# Rotator.net
KiCad netlist of a schematic drawn in EAGLE
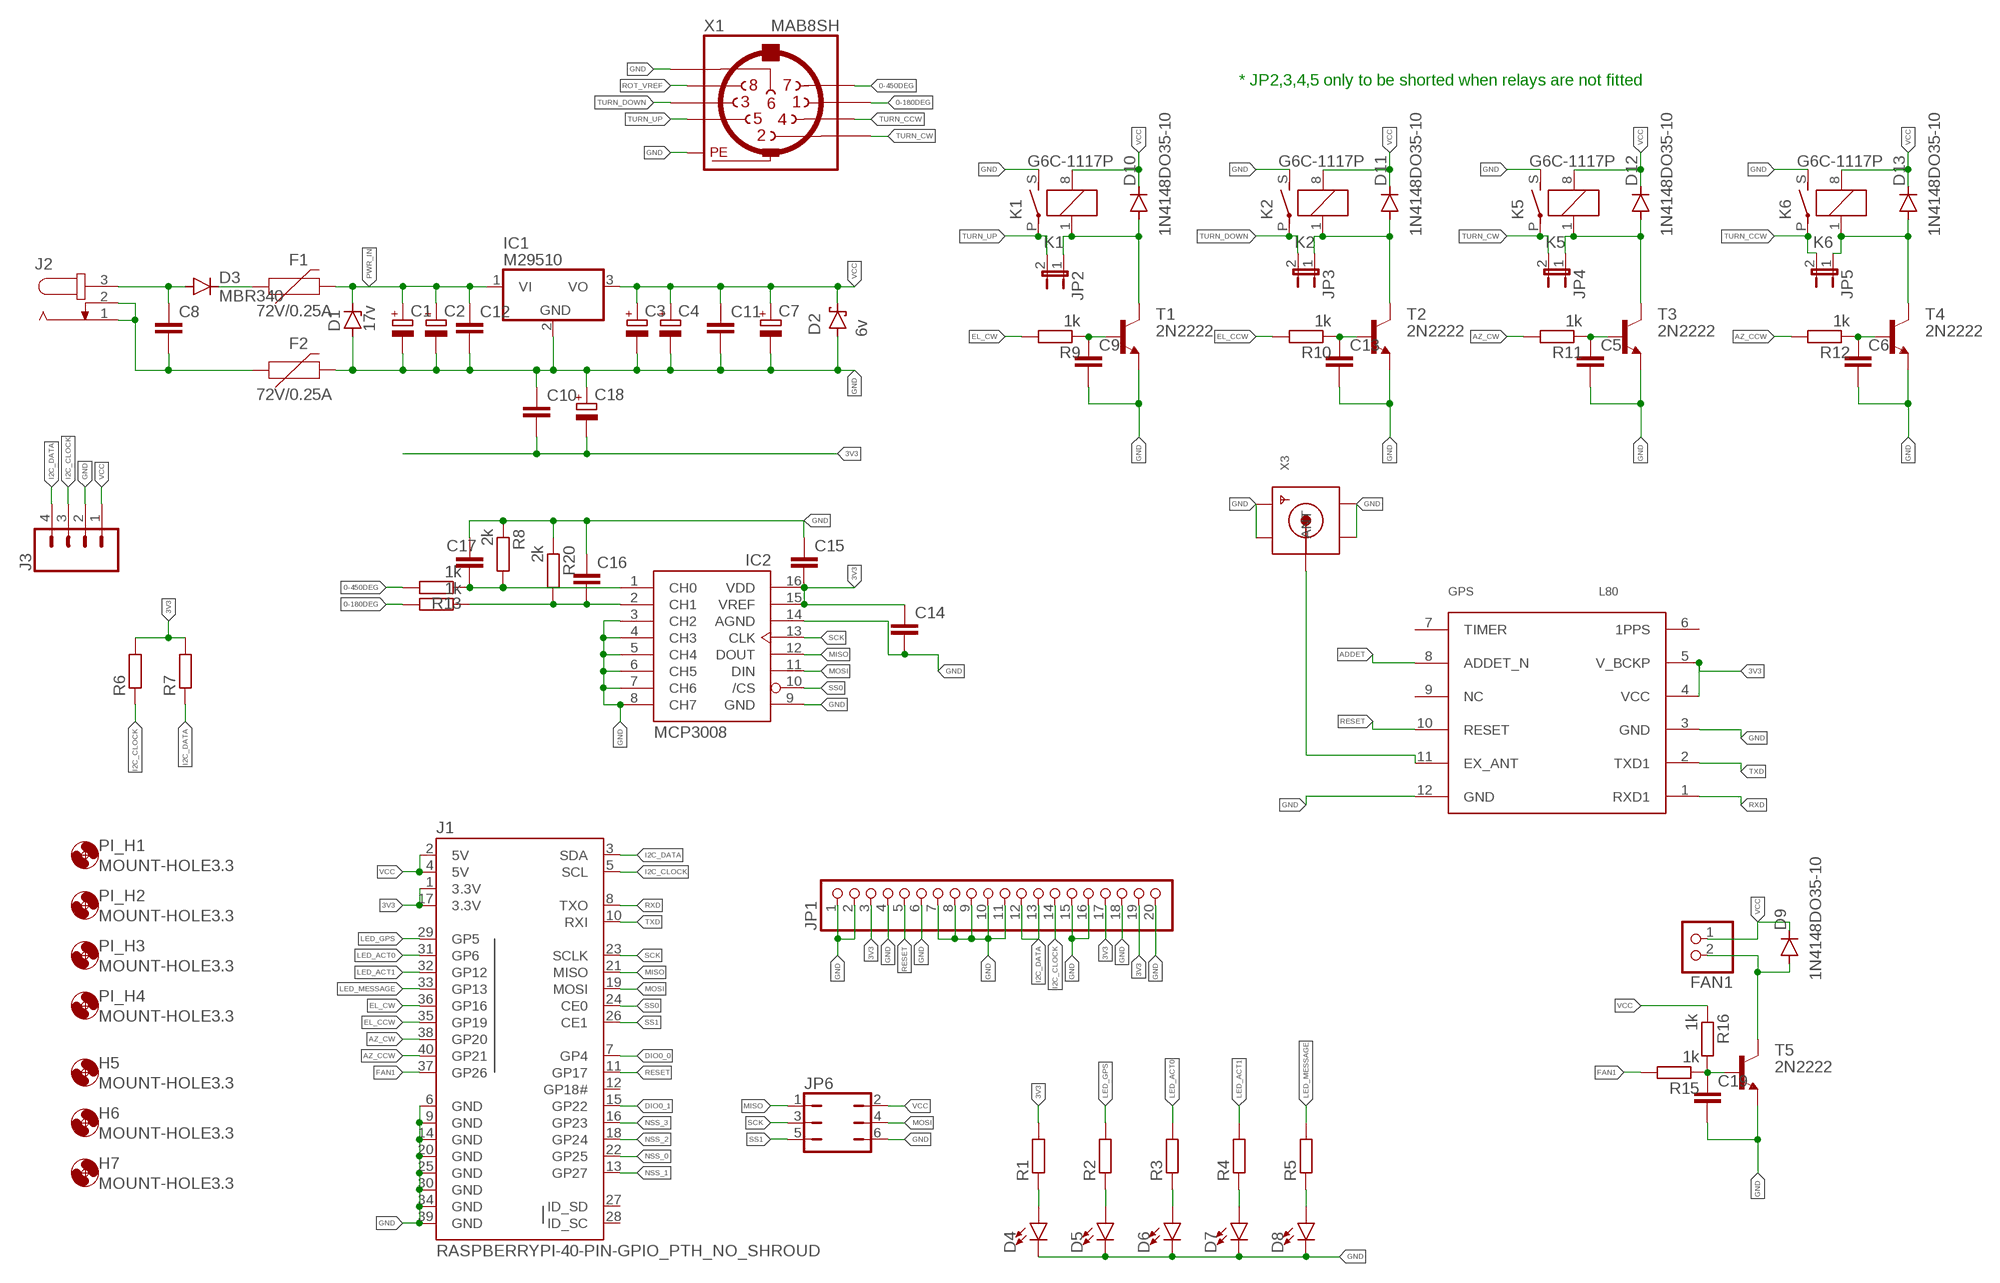
[diagram p0: schematic, sheet 1]

(export (version "E")
  (design (tool "Eeschema 10.0.6"))
  (components
    (comp (ref "C1")
      (value "CPOL-EUE5-8.5")
      (footprint "eagle-import:E5-8,5")
      (libsource (lib "eagle-import") (part "CPOL-EUE5-8.5"))
    )
    (comp (ref "C2")
      (value "CPOL-EUE5-8.5")
      (footprint "eagle-import:E5-8,5")
      (libsource (lib "eagle-import") (part "CPOL-EUE5-8.5"))
    )
    (comp (ref "C3")
      (value "CPOL-EUE2.5-7")
      (footprint "eagle-import:E2,5-7")
      (libsource (lib "eagle-import") (part "CPOL-EUE2.5-7"))
    )
    (comp (ref "C4")
      (value "CPOL-EUE2.5-7")
      (footprint "eagle-import:E2,5-7")
      (libsource (lib "eagle-import") (part "CPOL-EUE2.5-7"))
    )
    (comp (ref "C5")
      (value "C-EU050-025X075")
      (footprint "eagle-import:C050-025X075")
      (libsource (lib "eagle-import") (part "C-EU050-025X075"))
    )
    (comp (ref "C6")
      (value "C-EU050-025X075")
      (footprint "eagle-import:C050-025X075")
      (libsource (lib "eagle-import") (part "C-EU050-025X075"))
    )
    (comp (ref "C7")
      (value "CPOL-EUE2.5-7")
      (footprint "eagle-import:E2,5-7")
      (libsource (lib "eagle-import") (part "CPOL-EUE2.5-7"))
    )
    (comp (ref "C8")
      (value "C-EU050-025X075")
      (footprint "eagle-import:C050-025X075")
      (libsource (lib "eagle-import") (part "C-EU050-025X075"))
    )
    (comp (ref "C9")
      (value "C-EU050-025X075")
      (footprint "eagle-import:C050-025X075")
      (libsource (lib "eagle-import") (part "C-EU050-025X075"))
    )
    (comp (ref "C10")
      (value "C-EU050-025X075")
      (footprint "eagle-import:C050-025X075")
      (libsource (lib "eagle-import") (part "C-EU050-025X075"))
    )
    (comp (ref "C11")
      (value "C-EU050-025X075")
      (footprint "eagle-import:C050-025X075")
      (libsource (lib "eagle-import") (part "C-EU050-025X075"))
    )
    (comp (ref "C12")
      (value "C-EU050-025X075")
      (footprint "eagle-import:C050-025X075")
      (libsource (lib "eagle-import") (part "C-EU050-025X075"))
    )
    (comp (ref "C13")
      (value "C-EU050-025X075")
      (footprint "eagle-import:C050-025X075")
      (libsource (lib "eagle-import") (part "C-EU050-025X075"))
    )
    (comp (ref "C14")
      (value "C-EU050-025X075")
      (footprint "eagle-import:C050-025X075")
      (libsource (lib "eagle-import") (part "C-EU050-025X075"))
    )
    (comp (ref "C15")
      (value "C-EU050-025X075")
      (footprint "eagle-import:C050-025X075")
      (libsource (lib "eagle-import") (part "C-EU050-025X075"))
    )
    (comp (ref "C16")
      (value "C-EU050-025X075")
      (footprint "eagle-import:C050-025X075")
      (libsource (lib "eagle-import") (part "C-EU050-025X075"))
    )
    (comp (ref "C17")
      (value "C-EU050-025X075")
      (footprint "eagle-import:C050-025X075")
      (libsource (lib "eagle-import") (part "C-EU050-025X075"))
    )
    (comp (ref "C18")
      (value "CPOL-EUE2.5-7")
      (footprint "eagle-import:E2,5-7")
      (libsource (lib "eagle-import") (part "CPOL-EUE2.5-7"))
    )
    (comp (ref "C19")
      (value "C-EU050-025X075")
      (footprint "eagle-import:C050-025X075")
      (libsource (lib "eagle-import") (part "C-EU050-025X075"))
    )
    (comp (ref "D1")
      (value "17v")
      (footprint "eagle-import:F126Z12")
      (libsource (lib "eagle-import") (part "ZENER-DIODEF126-12"))
    )
    (comp (ref "D2")
      (value "6v")
      (footprint "eagle-import:F126Z12")
      (libsource (lib "eagle-import") (part "SCHOTTKY-DIODEF126Z12"))
    )
    (comp (ref "D3")
      (value "MBR340")
      (footprint "eagle-import:DO201-15")
      (libsource (lib "eagle-import") (part "1N5400"))
    )
    (comp (ref "D4")
      (value "LED3MM")
      (footprint "eagle-import:LED_3MM")
      (libsource (lib "eagle-import") (part "LED3MM"))
    )
    (comp (ref "D5")
      (value "LED3MM")
      (footprint "eagle-import:LED_3MM")
      (libsource (lib "eagle-import") (part "LED3MM"))
    )
    (comp (ref "D6")
      (value "LED3MM")
      (footprint "eagle-import:LED_3MM")
      (libsource (lib "eagle-import") (part "LED3MM"))
    )
    (comp (ref "D7")
      (value "LED3MM")
      (footprint "eagle-import:LED_3MM")
      (libsource (lib "eagle-import") (part "LED3MM"))
    )
    (comp (ref "D8")
      (value "LED3MM")
      (footprint "eagle-import:LED_3MM")
      (libsource (lib "eagle-import") (part "LED3MM"))
    )
    (comp (ref "D9")
      (value "1N4148DO35-10")
      (footprint "eagle-import:DO35-10")
      (libsource (lib "eagle-import") (part "1N4148DO35-10"))
    )
    (comp (ref "D10")
      (value "1N4148DO35-10")
      (footprint "eagle-import:DO35-10")
      (libsource (lib "eagle-import") (part "1N4148DO35-10"))
    )
    (comp (ref "D11")
      (value "1N4148DO35-10")
      (footprint "eagle-import:DO35-10")
      (libsource (lib "eagle-import") (part "1N4148DO35-10"))
    )
    (comp (ref "D12")
      (value "1N4148DO35-10")
      (footprint "eagle-import:DO35-10")
      (libsource (lib "eagle-import") (part "1N4148DO35-10"))
    )
    (comp (ref "D13")
      (value "1N4148DO35-10")
      (footprint "eagle-import:DO35-10")
      (libsource (lib "eagle-import") (part "1N4148DO35-10"))
    )
    (comp (ref "F1")
      (value "72V/0.25A")
      (footprint "eagle-import:PTH")
      (libsource (lib "eagle-import") (part "PPTC_PTH"))
    )
    (comp (ref "F2")
      (value "72V/0.25A")
      (footprint "eagle-import:PTH")
      (libsource (lib "eagle-import") (part "PPTC_PTH"))
    )
    (comp (ref "FAN1")
      (value "JST_2PIN-THM")
      (footprint "eagle-import:JST-PH-2-THM")
      (libsource (lib "eagle-import") (part "JST_2PIN-THM"))
    )
    (comp (ref "GPS")
      (value "L80")
      (footprint "eagle-import:L80")
      (libsource (lib "eagle-import") (part "L80"))
    )
    (comp (ref "H5")
      (value "MOUNT-HOLE3.3")
      (footprint "eagle-import:3,3")
      (libsource (lib "eagle-import") (part "MOUNT-HOLE3.3"))
    )
    (comp (ref "H6")
      (value "MOUNT-HOLE3.3")
      (footprint "eagle-import:3,3")
      (libsource (lib "eagle-import") (part "MOUNT-HOLE3.3"))
    )
    (comp (ref "H7")
      (value "MOUNT-HOLE3.3")
      (footprint "eagle-import:3,3")
      (libsource (lib "eagle-import") (part "MOUNT-HOLE3.3"))
    )
    (comp (ref "IC1")
      (value "M29510")
      (footprint "eagle-import:TO220H")
      (libsource (lib "eagle-import") (part "78T05"))
    )
    (comp (ref "IC2")
      (value "MCP3008")
      (footprint "eagle-import:DIL16")
      (libsource (lib "eagle-import") (part "MCP3008"))
    )
    (comp (ref "J1")
      (value "RASPBERRYPI-40-PIN-GPIO_PTH_NO_SHROUD")
      (footprint "eagle-import:2X20")
      (libsource (lib "eagle-import") (part "RASPBERRYPI-40-PIN-GPIO_PTH_NO_SHROUD"))
    )
    (comp (ref "J2")
      (value "JACK-PLUG0")
      (footprint "eagle-import:SPC4077")
      (libsource (lib "eagle-import") (part "JACK-PLUG0"))
    )
    (comp (ref "J3")
      (value "CONN_04")
      (footprint "eagle-import:1X04")
      (libsource (lib "eagle-import") (part "CONN_04"))
    )
    (comp (ref "JP1")
      (value "PINHD-1X20")
      (footprint "eagle-import:1X20")
      (libsource (lib "eagle-import") (part "PINHD-1X20"))
    )
    (comp (ref "JP2")
      (value "JP1E")
      (footprint "eagle-import:JP1")
      (libsource (lib "eagle-import") (part "JP1E"))
    )
    (comp (ref "JP3")
      (value "JP1E")
      (footprint "eagle-import:JP1")
      (libsource (lib "eagle-import") (part "JP1E"))
    )
    (comp (ref "JP4")
      (value "JP1E")
      (footprint "eagle-import:JP1")
      (libsource (lib "eagle-import") (part "JP1E"))
    )
    (comp (ref "JP5")
      (value "JP1E")
      (footprint "eagle-import:JP1")
      (libsource (lib "eagle-import") (part "JP1E"))
    )
    (comp (ref "JP6")
      (value "JP3Q")
      (footprint "eagle-import:JP3Q")
      (libsource (lib "eagle-import") (part "JP3Q"))
    )
    (comp (ref "K1")
      (value "G6C-1117P")
      (footprint "eagle-import:G6C-1117P")
      (libsource (lib "eagle-import") (part "G6C-1117P"))
    )
    (comp (ref "K2")
      (value "G6C-1117P")
      (footprint "eagle-import:G6C-1117P")
      (libsource (lib "eagle-import") (part "G6C-1117P"))
    )
    (comp (ref "K5")
      (value "G6C-1117P")
      (footprint "eagle-import:G6C-1117P")
      (libsource (lib "eagle-import") (part "G6C-1117P"))
    )
    (comp (ref "K6")
      (value "G6C-1117P")
      (footprint "eagle-import:G6C-1117P")
      (libsource (lib "eagle-import") (part "G6C-1117P"))
    )
    (comp (ref "PI_H1")
      (value "MOUNT-HOLE3.3")
      (footprint "eagle-import:3,3")
      (libsource (lib "eagle-import") (part "MOUNT-HOLE3.3"))
    )
    (comp (ref "PI_H2")
      (value "MOUNT-HOLE3.3")
      (footprint "eagle-import:3,3")
      (libsource (lib "eagle-import") (part "MOUNT-HOLE3.3"))
    )
    (comp (ref "PI_H3")
      (value "MOUNT-HOLE3.3")
      (footprint "eagle-import:3,3")
      (libsource (lib "eagle-import") (part "MOUNT-HOLE3.3"))
    )
    (comp (ref "PI_H4")
      (value "MOUNT-HOLE3.3")
      (footprint "eagle-import:3,3")
      (libsource (lib "eagle-import") (part "MOUNT-HOLE3.3"))
    )
    (comp (ref "R1")
      (value "R-EU_0207/10")
      (footprint "eagle-import:0207_10")
      (libsource (lib "eagle-import") (part "R-EU_0207/10"))
    )
    (comp (ref "R2")
      (value "R-EU_0207/10")
      (footprint "eagle-import:0207_10")
      (libsource (lib "eagle-import") (part "R-EU_0207/10"))
    )
    (comp (ref "R3")
      (value "R-EU_0207/10")
      (footprint "eagle-import:0207_10")
      (libsource (lib "eagle-import") (part "R-EU_0207/10"))
    )
    (comp (ref "R4")
      (value "R-EU_0207/10")
      (footprint "eagle-import:0207_10")
      (libsource (lib "eagle-import") (part "R-EU_0207/10"))
    )
    (comp (ref "R5")
      (value "R-EU_0207/10")
      (footprint "eagle-import:0207_10")
      (libsource (lib "eagle-import") (part "R-EU_0207/10"))
    )
    (comp (ref "R6")
      (value "R-EU_0207/10")
      (footprint "eagle-import:0207_10")
      (libsource (lib "eagle-import") (part "R-EU_0207/10"))
    )
    (comp (ref "R7")
      (value "R-EU_0207/10")
      (footprint "eagle-import:0207_10")
      (libsource (lib "eagle-import") (part "R-EU_0207/10"))
    )
    (comp (ref "R8")
      (value "2k")
      (footprint "eagle-import:0207_10")
      (libsource (lib "eagle-import") (part "R-EU_0207/10"))
    )
    (comp (ref "R9")
      (value "1k")
      (footprint "eagle-import:0207_10")
      (libsource (lib "eagle-import") (part "R-EU_0207/10"))
    )
    (comp (ref "R10")
      (value "1k")
      (footprint "eagle-import:0207_10")
      (libsource (lib "eagle-import") (part "R-EU_0207/10"))
    )
    (comp (ref "R11")
      (value "1k")
      (footprint "eagle-import:0207_10")
      (libsource (lib "eagle-import") (part "R-EU_0207/10"))
    )
    (comp (ref "R12")
      (value "1k")
      (footprint "eagle-import:0207_10")
      (libsource (lib "eagle-import") (part "R-EU_0207/10"))
    )
    (comp (ref "R13")
      (value "1k")
      (footprint "eagle-import:0207_10")
      (libsource (lib "eagle-import") (part "R-EU_0207/10"))
    )
    (comp (ref "R14")
      (value "1k")
      (footprint "eagle-import:0207_10")
      (libsource (lib "eagle-import") (part "R-EU_0207/10"))
    )
    (comp (ref "R15")
      (value "1k")
      (footprint "eagle-import:0207_10")
      (libsource (lib "eagle-import") (part "R-EU_0207/10"))
    )
    (comp (ref "R16")
      (value "1k")
      (footprint "eagle-import:0207_10")
      (libsource (lib "eagle-import") (part "R-EU_0207/10"))
    )
    (comp (ref "R20")
      (value "2k")
      (footprint "eagle-import:0207_10")
      (libsource (lib "eagle-import") (part "R-EU_0207/10"))
    )
    (comp (ref "T1")
      (value "2N2222")
      (footprint "eagle-import:TO92-EBC-OVAL")
      (libsource (lib "eagle-import") (part "2N2222"))
    )
    (comp (ref "T2")
      (value "2N2222")
      (footprint "eagle-import:TO92-EBC-OVAL")
      (libsource (lib "eagle-import") (part "2N2222"))
    )
    (comp (ref "T3")
      (value "2N2222")
      (footprint "eagle-import:TO92-EBC-OVAL")
      (libsource (lib "eagle-import") (part "2N2222"))
    )
    (comp (ref "T4")
      (value "2N2222")
      (footprint "eagle-import:TO92-EBC-OVAL")
      (libsource (lib "eagle-import") (part "2N2222"))
    )
    (comp (ref "T5")
      (value "2N2222")
      (footprint "eagle-import:TO92-EBC-OVAL")
      (libsource (lib "eagle-import") (part "2N2222"))
    )
    (comp (ref "X1")
      (value "MAB8SH")
      (footprint "eagle-import:MAB8SH")
      (fields (field (name "MF") "FARNELL") (field (name "MPN") "MAB 8 SH"))
      (libsource (lib "eagle-import") (part "MAB8SH"))
    )
    (comp (ref "X3")
      (value "SMACONNECTOR_EDGE")
      (footprint "eagle-import:SMA_EDGELAUNCH")
      (libsource (lib "eagle-import") (part "SMACONNECTOR_EDGE"))
    )
  )
  (nets
    (net (code "1") (name "0-180DEG") (class "Default")
      (node (ref "R14") (pin "2") (pinfunction "2_2") (pintype "passive"))
      (node (ref "X1") (pin "1") (pinfunction "1_1") (pintype "passive"))
    )
    (net (code "2") (name "0-450DEG") (class "Default")
      (node (ref "R13") (pin "2") (pinfunction "2_2") (pintype "passive"))
      (node (ref "X1") (pin "7") (pinfunction "7_7") (pintype "passive"))
    )
    (net (code "3") (name "3V3") (class "Default")
      (node (ref "C10") (pin "2") (pinfunction "2_2") (pintype "passive"))
      (node (ref "C14") (pin "1") (pinfunction "1_1") (pintype "passive"))
      (node (ref "C15") (pin "2") (pinfunction "2_2") (pintype "passive"))
      (node (ref "C18") (pin "-") (pinfunction "-_-") (pintype "passive"))
      (node (ref "GPS") (pin "4") (pinfunction "VCC_4") (pintype "bidirectional"))
      (node (ref "GPS") (pin "5") (pinfunction "V_BCKP_5") (pintype "bidirectional"))
      (node (ref "IC2") (pin "15") (pinfunction "VREF_15") (pintype "input"))
      (node (ref "IC2") (pin "16") (pinfunction "VDD_16") (pintype "power_in"))
      (node (ref "J1") (pin "1") (pinfunction "3.3V_1") (pintype "power_in"))
      (node (ref "J1") (pin "17") (pinfunction "3.3V_17") (pintype "power_in"))
      (node (ref "JP1") (pin "17") (pinfunction "17_17") (pintype "passive"))
      (node (ref "JP1") (pin "19") (pinfunction "19_19") (pintype "passive"))
      (node (ref "JP1") (pin "3") (pinfunction "3_3") (pintype "passive"))
      (node (ref "R1") (pin "2") (pinfunction "2_2") (pintype "passive"))
      (node (ref "R6") (pin "2") (pinfunction "2_2") (pintype "passive"))
      (node (ref "R7") (pin "2") (pinfunction "2_2") (pintype "passive"))
    )
    (net (code "4") (name "ADDET") (class "Default")
      (node (ref "GPS") (pin "8") (pinfunction "ADDET_N_8") (pintype "bidirectional"))
    )
    (net (code "5") (name "AZ_CCW") (class "Default")
      (node (ref "J1") (pin "40") (pinfunction "GP21_40") (pintype "bidirectional"))
      (node (ref "R12") (pin "2") (pinfunction "2_2") (pintype "passive"))
    )
    (net (code "6") (name "AZ_CW") (class "Default")
      (node (ref "J1") (pin "38") (pinfunction "GP20_38") (pintype "bidirectional"))
      (node (ref "R11") (pin "2") (pinfunction "2_2") (pintype "passive"))
    )
    (net (code "7") (name "DIO0_0") (class "Default")
      (node (ref "J1") (pin "7") (pinfunction "GP4_7") (pintype "bidirectional"))
    )
    (net (code "8") (name "DIO0_1") (class "Default")
      (node (ref "J1") (pin "15") (pinfunction "GP22_15") (pintype "bidirectional"))
    )
    (net (code "9") (name "EL_CCW") (class "Default")
      (node (ref "J1") (pin "35") (pinfunction "GP19_35") (pintype "bidirectional"))
      (node (ref "R10") (pin "2") (pinfunction "2_2") (pintype "passive"))
    )
    (net (code "10") (name "EL_CW") (class "Default")
      (node (ref "J1") (pin "36") (pinfunction "GP16_36") (pintype "bidirectional"))
      (node (ref "R9") (pin "2") (pinfunction "2_2") (pintype "passive"))
    )
    (net (code "11") (name "FAN1") (class "Default")
      (node (ref "J1") (pin "37") (pinfunction "GP26_37") (pintype "bidirectional"))
      (node (ref "R15") (pin "2") (pinfunction "2_2") (pintype "passive"))
    )
    (net (code "12") (name "GND") (class "Default")
      (node (ref "C1") (pin "-") (pinfunction "-_-") (pintype "passive"))
      (node (ref "C10") (pin "1") (pinfunction "1_1") (pintype "passive"))
      (node (ref "C11") (pin "2") (pinfunction "2_2") (pintype "passive"))
      (node (ref "C12") (pin "2") (pinfunction "2_2") (pintype "passive"))
      (node (ref "C13") (pin "2") (pinfunction "2_2") (pintype "passive"))
      (node (ref "C14") (pin "2") (pinfunction "2_2") (pintype "passive"))
      (node (ref "C15") (pin "1") (pinfunction "1_1") (pintype "passive"))
      (node (ref "C16") (pin "1") (pinfunction "1_1") (pintype "passive"))
      (node (ref "C17") (pin "1") (pinfunction "1_1") (pintype "passive"))
      (node (ref "C18") (pin "+") (pinfunction "+_+") (pintype "passive"))
      (node (ref "C19") (pin "2") (pinfunction "2_2") (pintype "passive"))
      (node (ref "C2") (pin "-") (pinfunction "-_-") (pintype "passive"))
      (node (ref "C3") (pin "-") (pinfunction "-_-") (pintype "passive"))
      (node (ref "C4") (pin "-") (pinfunction "-_-") (pintype "passive"))
      (node (ref "C5") (pin "2") (pinfunction "2_2") (pintype "passive"))
      (node (ref "C6") (pin "2") (pinfunction "2_2") (pintype "passive"))
      (node (ref "C7") (pin "-") (pinfunction "-_-") (pintype "passive"))
      (node (ref "C9") (pin "2") (pinfunction "2_2") (pintype "passive"))
      (node (ref "D1") (pin "A") (pinfunction "A_A") (pintype "passive"))
      (node (ref "D2") (pin "A") (pinfunction "A_A") (pintype "passive"))
      (node (ref "D4") (pin "K") (pinfunction "C_K") (pintype "passive"))
      (node (ref "D5") (pin "K") (pinfunction "C_K") (pintype "passive"))
      (node (ref "D6") (pin "K") (pinfunction "C_K") (pintype "passive"))
      (node (ref "D7") (pin "K") (pinfunction "C_K") (pintype "passive"))
      (node (ref "D8") (pin "K") (pinfunction "C_K") (pintype "passive"))
      (node (ref "F2") (pin "P$2") (pinfunction "2_P$2") (pintype "bidirectional"))
      (node (ref "GPS") (pin "12") (pinfunction "GND_12") (pintype "bidirectional"))
      (node (ref "GPS") (pin "3") (pinfunction "GND_3") (pintype "bidirectional"))
      (node (ref "IC1") (pin "2") (pinfunction "GND_2") (pintype "passive"))
      (node (ref "IC2") (pin "14") (pinfunction "AGND_14") (pintype "power_in"))
      (node (ref "IC2") (pin "3") (pinfunction "CH2_3") (pintype "input"))
      (node (ref "IC2") (pin "4") (pinfunction "CH3_4") (pintype "input"))
      (node (ref "IC2") (pin "5") (pinfunction "CH4_5") (pintype "input"))
      (node (ref "IC2") (pin "6") (pinfunction "CH5_6") (pintype "input"))
      (node (ref "IC2") (pin "7") (pinfunction "CH6_7") (pintype "input"))
      (node (ref "IC2") (pin "8") (pinfunction "CH7_8") (pintype "input"))
      (node (ref "IC2") (pin "9") (pinfunction "GND_9") (pintype "power_in"))
      (node (ref "J1") (pin "14") (pinfunction "GND_14") (pintype "power_in"))
      (node (ref "J1") (pin "20") (pinfunction "GND_20") (pintype "power_in"))
      (node (ref "J1") (pin "25") (pinfunction "GND_25") (pintype "power_in"))
      (node (ref "J1") (pin "30") (pinfunction "GND_30") (pintype "power_in"))
      (node (ref "J1") (pin "34") (pinfunction "GND_34") (pintype "power_in"))
      (node (ref "J1") (pin "39") (pinfunction "GND_39") (pintype "power_in"))
      (node (ref "J1") (pin "6") (pinfunction "GND_6") (pintype "power_in"))
      (node (ref "J1") (pin "9") (pinfunction "GND_9") (pintype "power_in"))
      (node (ref "J3") (pin "2") (pinfunction "2_2") (pintype "passive"))
      (node (ref "JP1") (pin "1") (pinfunction "1_1") (pintype "passive"))
      (node (ref "JP1") (pin "10") (pinfunction "10_10") (pintype "passive"))
      (node (ref "JP1") (pin "11") (pinfunction "11_11") (pintype "passive"))
      (node (ref "JP1") (pin "15") (pinfunction "15_15") (pintype "passive"))
      (node (ref "JP1") (pin "16") (pinfunction "16_16") (pintype "passive"))
      (node (ref "JP1") (pin "18") (pinfunction "18_18") (pintype "passive"))
      (node (ref "JP1") (pin "2") (pinfunction "2_2") (pintype "passive"))
      (node (ref "JP1") (pin "20") (pinfunction "20_20") (pintype "passive"))
      (node (ref "JP1") (pin "4") (pinfunction "4_4") (pintype "passive"))
      (node (ref "JP1") (pin "6") (pinfunction "6_6") (pintype "passive"))
      (node (ref "JP1") (pin "7") (pinfunction "7_7") (pintype "passive"))
      (node (ref "JP1") (pin "8") (pinfunction "8_8") (pintype "passive"))
      (node (ref "JP1") (pin "9") (pinfunction "9_9") (pintype "passive"))
      (node (ref "JP6") (pin "6") (pinfunction "6_6") (pintype "passive"))
      (node (ref "K1") (pin "S") (pinfunction "S_S") (pintype "passive"))
      (node (ref "K2") (pin "S") (pinfunction "S_S") (pintype "passive"))
      (node (ref "K5") (pin "S") (pinfunction "S_S") (pintype "passive"))
      (node (ref "K6") (pin "S") (pinfunction "S_S") (pintype "passive"))
      (node (ref "R20") (pin "1") (pinfunction "1_1") (pintype "passive"))
      (node (ref "R8") (pin "1") (pinfunction "1_1") (pintype "passive"))
      (node (ref "T1") (pin "E") (pinfunction "E_E") (pintype "passive"))
      (node (ref "T2") (pin "E") (pinfunction "E_E") (pintype "passive"))
      (node (ref "T3") (pin "E") (pinfunction "E_E") (pintype "passive"))
      (node (ref "T4") (pin "E") (pinfunction "E_E") (pintype "passive"))
      (node (ref "T5") (pin "E") (pinfunction "E_E") (pintype "passive"))
      (node (ref "X1") (pin "6") (pinfunction "6_6") (pintype "passive"))
      (node (ref "X1") (pin "PE") (pinfunction "PE_PE") (pintype "power_in"))
      (node (ref "X1") (pin "PE@") (pinfunction "PE_PE@") (pintype "power_in"))
      (node (ref "X3") (pin "GND@1") (pinfunction "GND4_GND@1") (pintype "power_in"))
      (node (ref "X3") (pin "GND@2") (pinfunction "GND3_GND@2") (pintype "power_in"))
      (node (ref "X3") (pin "GND@3") (pinfunction "GND2_GND@3") (pintype "power_in"))
      (node (ref "X3") (pin "GND@4") (pinfunction "GND1_GND@4") (pintype "power_in"))
    )
    (net (code "13") (name "I2C_CLOCK") (class "Default")
      (node (ref "J1") (pin "5") (pinfunction "SCL_5") (pintype "bidirectional"))
      (node (ref "J3") (pin "3") (pinfunction "3_3") (pintype "passive"))
      (node (ref "JP1") (pin "14") (pinfunction "14_14") (pintype "passive"))
      (node (ref "R6") (pin "1") (pinfunction "1_1") (pintype "passive"))
    )
    (net (code "14") (name "I2C_DATA") (class "Default")
      (node (ref "J1") (pin "3") (pinfunction "SDA_3") (pintype "bidirectional"))
      (node (ref "J3") (pin "4") (pinfunction "4_4") (pintype "passive"))
      (node (ref "JP1") (pin "12") (pinfunction "12_12") (pintype "passive"))
      (node (ref "JP1") (pin "13") (pinfunction "13_13") (pintype "passive"))
      (node (ref "R7") (pin "1") (pinfunction "1_1") (pintype "passive"))
    )
    (net (code "15") (name "LED_ACT0") (class "Default")
      (node (ref "J1") (pin "31") (pinfunction "GP6_31") (pintype "bidirectional"))
      (node (ref "R3") (pin "2") (pinfunction "2_2") (pintype "passive"))
    )
    (net (code "16") (name "LED_ACT1") (class "Default")
      (node (ref "J1") (pin "32") (pinfunction "GP12_32") (pintype "bidirectional"))
      (node (ref "R4") (pin "2") (pinfunction "2_2") (pintype "passive"))
    )
    (net (code "17") (name "LED_GPS") (class "Default")
      (node (ref "J1") (pin "29") (pinfunction "GP5_29") (pintype "bidirectional"))
      (node (ref "R2") (pin "2") (pinfunction "2_2") (pintype "passive"))
    )
    (net (code "18") (name "LED_MESSAGE") (class "Default")
      (node (ref "J1") (pin "33") (pinfunction "GP13_33") (pintype "bidirectional"))
      (node (ref "R5") (pin "2") (pinfunction "2_2") (pintype "passive"))
    )
    (net (code "19") (name "MISO") (class "Default")
      (node (ref "IC2") (pin "12") (pinfunction "DOUT_12") (pintype "output"))
      (node (ref "J1") (pin "21") (pinfunction "MISO_21") (pintype "input"))
      (node (ref "JP6") (pin "1") (pinfunction "1_1") (pintype "passive"))
    )
    (net (code "20") (name "MOSI") (class "Default")
      (node (ref "IC2") (pin "11") (pinfunction "DIN_11") (pintype "input"))
      (node (ref "J1") (pin "19") (pinfunction "MOSI_19") (pintype "output"))
      (node (ref "JP6") (pin "4") (pinfunction "4_4") (pintype "passive"))
    )
    (net (code "21") (name "NSS_0") (class "Default")
      (node (ref "J1") (pin "22") (pinfunction "GP25_22") (pintype "bidirectional"))
    )
    (net (code "22") (name "NSS_1") (class "Default")
      (node (ref "J1") (pin "13") (pinfunction "GP27_13") (pintype "bidirectional"))
    )
    (net (code "23") (name "NSS_2") (class "Default")
      (node (ref "J1") (pin "18") (pinfunction "GP24_18") (pintype "bidirectional"))
    )
    (net (code "24") (name "NSS_3") (class "Default")
      (node (ref "J1") (pin "16") (pinfunction "GP23_16") (pintype "bidirectional"))
    )
    (net (code "25") (name "Net-(C5-Pad1)") (class "Default")
      (node (ref "C5") (pin "1") (pinfunction "1_1") (pintype "passive"))
      (node (ref "R11") (pin "1") (pinfunction "1_1") (pintype "passive"))
      (node (ref "T3") (pin "B") (pinfunction "B_B") (pintype "passive"))
    )
    (net (code "26") (name "Net-(C6-Pad1)") (class "Default")
      (node (ref "C6") (pin "1") (pinfunction "1_1") (pintype "passive"))
      (node (ref "R12") (pin "1") (pinfunction "1_1") (pintype "passive"))
      (node (ref "T4") (pin "B") (pinfunction "B_B") (pintype "passive"))
    )
    (net (code "27") (name "Net-(C8-Pad1)") (class "Default")
      (node (ref "C8") (pin "1") (pinfunction "1_1") (pintype "passive"))
      (node (ref "D3") (pin "A") (pinfunction "A_A") (pintype "passive"))
      (node (ref "J2") (pin "3") (pinfunction "3_3") (pintype "passive"))
    )
    (net (code "28") (name "Net-(C9-Pad1)") (class "Default")
      (node (ref "C9") (pin "1") (pinfunction "1_1") (pintype "passive"))
      (node (ref "R9") (pin "1") (pinfunction "1_1") (pintype "passive"))
      (node (ref "T1") (pin "B") (pinfunction "B_B") (pintype "passive"))
    )
    (net (code "29") (name "Net-(C13-Pad1)") (class "Default")
      (node (ref "C13") (pin "1") (pinfunction "1_1") (pintype "passive"))
      (node (ref "R10") (pin "1") (pinfunction "1_1") (pintype "passive"))
      (node (ref "T2") (pin "B") (pinfunction "B_B") (pintype "passive"))
    )
    (net (code "30") (name "Net-(C19-Pad1)") (class "Default")
      (node (ref "C19") (pin "1") (pinfunction "1_1") (pintype "passive"))
      (node (ref "R15") (pin "1") (pinfunction "1_1") (pintype "passive"))
      (node (ref "R16") (pin "2") (pinfunction "2_2") (pintype "passive"))
      (node (ref "T5") (pin "B") (pinfunction "B_B") (pintype "passive"))
    )
    (net (code "31") (name "Net-(D4-PadA)") (class "Default")
      (node (ref "D4") (pin "A") (pinfunction "A_A") (pintype "passive"))
      (node (ref "R1") (pin "1") (pinfunction "1_1") (pintype "passive"))
    )
    (net (code "32") (name "Net-(D5-PadA)") (class "Default")
      (node (ref "D5") (pin "A") (pinfunction "A_A") (pintype "passive"))
      (node (ref "R2") (pin "1") (pinfunction "1_1") (pintype "passive"))
    )
    (net (code "33") (name "Net-(D6-PadA)") (class "Default")
      (node (ref "D6") (pin "A") (pinfunction "A_A") (pintype "passive"))
      (node (ref "R3") (pin "1") (pinfunction "1_1") (pintype "passive"))
    )
    (net (code "34") (name "Net-(D7-PadA)") (class "Default")
      (node (ref "D7") (pin "A") (pinfunction "A_A") (pintype "passive"))
      (node (ref "R4") (pin "1") (pinfunction "1_1") (pintype "passive"))
    )
    (net (code "35") (name "Net-(D8-PadA)") (class "Default")
      (node (ref "D8") (pin "A") (pinfunction "A_A") (pintype "passive"))
      (node (ref "R5") (pin "1") (pinfunction "1_1") (pintype "passive"))
    )
    (net (code "36") (name "Net-(D10-PadA)") (class "Default")
      (node (ref "D10") (pin "A") (pinfunction "A_A") (pintype "passive"))
      (node (ref "JP2") (pin "1") (pinfunction "1_1") (pintype "passive"))
      (node (ref "K1") (pin "1") (pinfunction "1_1") (pintype "passive"))
      (node (ref "T1") (pin "C") (pinfunction "C_C") (pintype "passive"))
    )
    (net (code "37") (name "Net-(D11-PadA)") (class "Default")
      (node (ref "D11") (pin "A") (pinfunction "A_A") (pintype "passive"))
      (node (ref "JP3") (pin "1") (pinfunction "1_1") (pintype "passive"))
      (node (ref "K2") (pin "1") (pinfunction "1_1") (pintype "passive"))
      (node (ref "T2") (pin "C") (pinfunction "C_C") (pintype "passive"))
    )
    (net (code "38") (name "Net-(D12-PadA)") (class "Default")
      (node (ref "D12") (pin "A") (pinfunction "A_A") (pintype "passive"))
      (node (ref "JP4") (pin "1") (pinfunction "1_1") (pintype "passive"))
      (node (ref "K5") (pin "1") (pinfunction "1_1") (pintype "passive"))
      (node (ref "T3") (pin "C") (pinfunction "C_C") (pintype "passive"))
    )
    (net (code "39") (name "Net-(D13-PadA)") (class "Default")
      (node (ref "D13") (pin "A") (pinfunction "A_A") (pintype "passive"))
      (node (ref "JP5") (pin "1") (pinfunction "1_1") (pintype "passive"))
      (node (ref "K6") (pin "1") (pinfunction "1_1") (pintype "passive"))
      (node (ref "T4") (pin "C") (pinfunction "C_C") (pintype "passive"))
    )
    (net (code "40") (name "Net-(F1-1)") (class "Default")
      (node (ref "D3") (pin "C") (pinfunction "C_C") (pintype "passive"))
      (node (ref "F1") (pin "P$1") (pinfunction "1_P$1") (pintype "bidirectional"))
    )
    (net (code "41") (name "Net-(F2-1)") (class "Default")
      (node (ref "C8") (pin "2") (pinfunction "2_2") (pintype "passive"))
      (node (ref "F2") (pin "P$1") (pinfunction "1_P$1") (pintype "bidirectional"))
      (node (ref "J2") (pin "1") (pinfunction "1_1") (pintype "passive"))
      (node (ref "J2") (pin "2") (pinfunction "2_2") (pintype "passive"))
    )
    (net (code "42") (name "Net-(FAN1-1)") (class "Default")
      (node (ref "D9") (pin "A") (pinfunction "A_A") (pintype "passive"))
      (node (ref "FAN1") (pin "2") (pinfunction "1_2") (pintype "passive"))
      (node (ref "T5") (pin "C") (pinfunction "C_C") (pintype "passive"))
    )
    (net (code "43") (name "Net-(GPS-EX_ANT)") (class "Default")
      (node (ref "GPS") (pin "11") (pinfunction "EX_ANT_11") (pintype "bidirectional"))
      (node (ref "X3") (pin "P") (pinfunction "ANT_P") (pintype "bidirectional"))
    )
    (net (code "44") (name "Net-(IC2-CH0)") (class "Default")
      (node (ref "C17") (pin "2") (pinfunction "2_2") (pintype "passive"))
      (node (ref "IC2") (pin "1") (pinfunction "CH0_1") (pintype "input"))
      (node (ref "R13") (pin "1") (pinfunction "1_1") (pintype "passive"))
      (node (ref "R8") (pin "2") (pinfunction "2_2") (pintype "passive"))
    )
    (net (code "45") (name "Net-(IC2-CH1)") (class "Default")
      (node (ref "C16") (pin "2") (pinfunction "2_2") (pintype "passive"))
      (node (ref "IC2") (pin "2") (pinfunction "CH1_2") (pintype "input"))
      (node (ref "R14") (pin "1") (pinfunction "1_1") (pintype "passive"))
      (node (ref "R20") (pin "2") (pinfunction "2_2") (pintype "passive"))
    )
    (net (code "46") (name "PWR_IN") (class "Default")
      (node (ref "C1") (pin "+") (pinfunction "+_+") (pintype "passive"))
      (node (ref "C12") (pin "1") (pinfunction "1_1") (pintype "passive"))
      (node (ref "C2") (pin "+") (pinfunction "+_+") (pintype "passive"))
      (node (ref "D1") (pin "C") (pinfunction "C_C") (pintype "passive"))
      (node (ref "F1") (pin "P$2") (pinfunction "2_P$2") (pintype "bidirectional"))
      (node (ref "IC1") (pin "1") (pinfunction "VI_1") (pintype "input"))
    )
    (net (code "47") (name "RESET") (class "Default")
      (node (ref "GPS") (pin "10") (pinfunction "RESET_10") (pintype "bidirectional"))
      (node (ref "J1") (pin "11") (pinfunction "GP17_11") (pintype "bidirectional"))
      (node (ref "JP1") (pin "5") (pinfunction "5_5") (pintype "passive"))
    )
    (net (code "48") (name "ROT_VREF") (class "Default")
      (node (ref "X1") (pin "8") (pinfunction "8_8") (pintype "passive"))
    )
    (net (code "49") (name "RXD") (class "Default")
      (node (ref "GPS") (pin "1") (pinfunction "RXD1_1") (pintype "bidirectional"))
      (node (ref "J1") (pin "8") (pinfunction "TXO_8") (pintype "output"))
    )
    (net (code "50") (name "SCK") (class "Default")
      (node (ref "IC2") (pin "13") (pinfunction "CLK_13") (pintype "input"))
      (node (ref "J1") (pin "23") (pinfunction "SCLK_23") (pintype "output"))
      (node (ref "JP6") (pin "3") (pinfunction "3_3") (pintype "passive"))
    )
    (net (code "51") (name "SS0") (class "Default")
      (node (ref "IC2") (pin "10") (pinfunction "/CS_10") (pintype "input"))
      (node (ref "J1") (pin "24") (pinfunction "CE0_24") (pintype "output"))
    )
    (net (code "52") (name "SS1") (class "Default")
      (node (ref "J1") (pin "26") (pinfunction "CE1_26") (pintype "output"))
      (node (ref "JP6") (pin "5") (pinfunction "5_5") (pintype "passive"))
    )
    (net (code "53") (name "TURN_CCW") (class "Default")
      (node (ref "JP5") (pin "2") (pinfunction "2_2") (pintype "passive"))
      (node (ref "K6") (pin "P") (pinfunction "P_P") (pintype "passive"))
      (node (ref "X1") (pin "4") (pinfunction "4_4") (pintype "passive"))
    )
    (net (code "54") (name "TURN_CW") (class "Default")
      (node (ref "JP4") (pin "2") (pinfunction "2_2") (pintype "passive"))
      (node (ref "K5") (pin "P") (pinfunction "P_P") (pintype "passive"))
      (node (ref "X1") (pin "2") (pinfunction "2_2") (pintype "passive"))
    )
    (net (code "55") (name "TURN_DOWN") (class "Default")
      (node (ref "JP3") (pin "2") (pinfunction "2_2") (pintype "passive"))
      (node (ref "K2") (pin "P") (pinfunction "P_P") (pintype "passive"))
      (node (ref "X1") (pin "3") (pinfunction "3_3") (pintype "passive"))
    )
    (net (code "56") (name "TURN_UP") (class "Default")
      (node (ref "JP2") (pin "2") (pinfunction "2_2") (pintype "passive"))
      (node (ref "K1") (pin "P") (pinfunction "P_P") (pintype "passive"))
      (node (ref "X1") (pin "5") (pinfunction "5_5") (pintype "passive"))
    )
    (net (code "57") (name "TXD") (class "Default")
      (node (ref "GPS") (pin "2") (pinfunction "TXD1_2") (pintype "bidirectional"))
      (node (ref "J1") (pin "10") (pinfunction "RXI_10") (pintype "input"))
    )
    (net (code "58") (name "VCC") (class "Default")
      (node (ref "C11") (pin "1") (pinfunction "1_1") (pintype "passive"))
      (node (ref "C3") (pin "+") (pinfunction "+_+") (pintype "passive"))
      (node (ref "C4") (pin "+") (pinfunction "+_+") (pintype "passive"))
      (node (ref "C7") (pin "+") (pinfunction "+_+") (pintype "passive"))
      (node (ref "D10") (pin "C") (pinfunction "C_C") (pintype "passive"))
      (node (ref "D11") (pin "C") (pinfunction "C_C") (pintype "passive"))
      (node (ref "D12") (pin "C") (pinfunction "C_C") (pintype "passive"))
      (node (ref "D13") (pin "C") (pinfunction "C_C") (pintype "passive"))
      (node (ref "D2") (pin "C") (pinfunction "C_C") (pintype "passive"))
      (node (ref "D9") (pin "C") (pinfunction "C_C") (pintype "passive"))
      (node (ref "FAN1") (pin "1") (pinfunction "2_1") (pintype "passive"))
      (node (ref "IC1") (pin "3") (pinfunction "VO_3") (pintype "passive"))
      (node (ref "J1") (pin "2") (pinfunction "5V_2") (pintype "power_in"))
      (node (ref "J1") (pin "4") (pinfunction "5V_4") (pintype "power_in"))
      (node (ref "J3") (pin "1") (pinfunction "1_1") (pintype "passive"))
      (node (ref "JP6") (pin "2") (pinfunction "2_2") (pintype "passive"))
      (node (ref "K1") (pin "8") (pinfunction "2_8") (pintype "passive"))
      (node (ref "K2") (pin "8") (pinfunction "2_8") (pintype "passive"))
      (node (ref "K5") (pin "8") (pinfunction "2_8") (pintype "passive"))
      (node (ref "K6") (pin "8") (pinfunction "2_8") (pintype "passive"))
      (node (ref "R16") (pin "1") (pinfunction "1_1") (pintype "passive"))
    )
    (net (code "59") (name "unconnected-(GPS-1PPS-Pad6)") (class "Default")
      (node (ref "GPS") (pin "6") (pinfunction "1PPS_6") (pintype "bidirectional"))
    )
    (net (code "60") (name "unconnected-(GPS-NC-Pad9)") (class "Default")
      (node (ref "GPS") (pin "9") (pinfunction "NC_9") (pintype "bidirectional"))
    )
    (net (code "61") (name "unconnected-(GPS-TIMER-Pad7)") (class "Default")
      (node (ref "GPS") (pin "7") (pinfunction "TIMER_7") (pintype "bidirectional"))
    )
    (net (code "62") (name "unconnected-(J1-GP18#-Pad12)") (class "Default")
      (node (ref "J1") (pin "12") (pinfunction "GP18#_12") (pintype "bidirectional"))
    )
    (net (code "63") (name "unconnected-(J1-ID_SC-Pad28)") (class "Default")
      (node (ref "J1") (pin "28") (pinfunction "ID_SC_28") (pintype "bidirectional"))
    )
    (net (code "64") (name "unconnected-(J1-ID_SD-Pad27)") (class "Default")
      (node (ref "J1") (pin "27") (pinfunction "ID_SD_27") (pintype "bidirectional"))
    )
  )
)
